# Raptor.net
KiCad netlist of a schematic drawn in Altium Designer
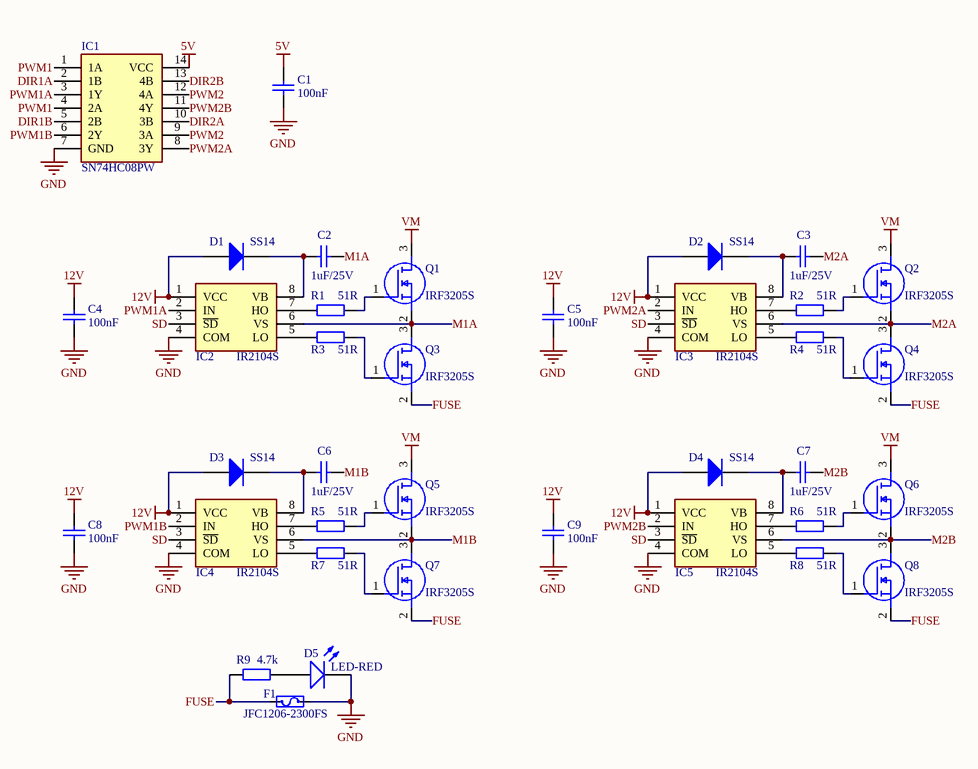
[diagram p0: Raptor.SchDoc]

(export (version "E")
  (design (tool "Eeschema 10.0.6"))
  (components
    (comp (ref "C1")
      (value "100nF")
      (footprint "CAP-0603")
      (description "贴片电容")
      (libsource (lib "Power_Lib_Altium") (part "CAP"))
    )
    (comp (ref "C2")
      (value "1uF/25V")
      (footprint "CAP-0603")
      (description "贴片电容")
      (libsource (lib "Power_Lib_Altium") (part "CAP"))
    )
    (comp (ref "C3")
      (value "1uF/25V")
      (footprint "CAP-0603")
      (description "贴片电容")
      (libsource (lib "Power_Lib_Altium") (part "CAP"))
    )
    (comp (ref "C4")
      (value "100nF")
      (footprint "CAP-0603")
      (description "贴片电容")
      (libsource (lib "Power_Lib_Altium") (part "CAP"))
    )
    (comp (ref "C5")
      (value "100nF")
      (footprint "CAP-0603")
      (description "贴片电容")
      (libsource (lib "Power_Lib_Altium") (part "CAP"))
    )
    (comp (ref "C6")
      (value "1uF/25V")
      (footprint "CAP-0603")
      (description "贴片电容")
      (libsource (lib "Power_Lib_Altium") (part "CAP"))
    )
    (comp (ref "C7")
      (value "1uF/25V")
      (footprint "CAP-0603")
      (description "贴片电容")
      (libsource (lib "Power_Lib_Altium") (part "CAP"))
    )
    (comp (ref "C8")
      (value "100nF")
      (footprint "CAP-0603")
      (description "贴片电容")
      (libsource (lib "Power_Lib_Altium") (part "CAP"))
    )
    (comp (ref "C9")
      (value "100nF")
      (footprint "CAP-0603")
      (description "贴片电容")
      (libsource (lib "Power_Lib_Altium") (part "CAP"))
    )
    (comp (ref "D1")
      (value "SS14")
      (footprint "DO-214AC_SMA")
      (description "二极管")
      (libsource (lib "Power_Lib_Altium") (part "DIODE"))
    )
    (comp (ref "D2")
      (value "SS14")
      (footprint "DO-214AC_SMA")
      (description "二极管")
      (libsource (lib "Power_Lib_Altium") (part "DIODE"))
    )
    (comp (ref "D3")
      (value "SS14")
      (footprint "DO-214AC_SMA")
      (description "二极管")
      (libsource (lib "Power_Lib_Altium") (part "DIODE"))
    )
    (comp (ref "D4")
      (value "SS14")
      (footprint "DO-214AC_SMA")
      (description "二极管")
      (libsource (lib "Power_Lib_Altium") (part "DIODE"))
    )
    (comp (ref "D5")
      (value "LED-RED")
      (footprint "LED-0603")
      (description "发光二极管")
      (libsource (lib "Power_Lib_Altium") (part "LED"))
    )
    (comp (ref "F1")
      (value "JFC1206-2300FS")
      (footprint "FUSE_1206")
      (description "一次性贴片保险丝")
      (libsource (lib "Power_Lib_Altium") (part "Fuse"))
    )
    (comp (ref "IC1")
      (value "SN74HC08PW")
      (footprint "TSSOP14")
      (description "Texas Instruments SN74HCT08PW")
      (fields (field (name "MANUFACTURER_PART_NUMBER") "SN74HCT08PW"))
      (libsource (lib "Power_Lib_Altium") (part "SN74HC08PW"))
    )
    (comp (ref "IC2")
      (value "IR2104S")
      (footprint "SOIC_8")
      (description "IC GATE DRVR HALF-BRIDGE 8SOIC")
      (libsource (lib "Power_Lib_Altium") (part "IR2104S"))
    )
    (comp (ref "IC3")
      (value "IR2104S")
      (footprint "SOIC_8")
      (description "IC GATE DRVR HALF-BRIDGE 8SOIC")
      (libsource (lib "Power_Lib_Altium") (part "IR2104S"))
    )
    (comp (ref "IC4")
      (value "IR2104S")
      (footprint "SOIC_8")
      (description "IC GATE DRVR HALF-BRIDGE 8SOIC")
      (libsource (lib "Power_Lib_Altium") (part "IR2104S"))
    )
    (comp (ref "IC5")
      (value "IR2104S")
      (footprint "SOIC_8")
      (description "IC GATE DRVR HALF-BRIDGE 8SOIC")
      (libsource (lib "Power_Lib_Altium") (part "IR2104S"))
    )
    (comp (ref "Q1")
      (value "IRF3205S")
      (footprint "D2PAK-3")
      (description "N 沟道 MOS")
      (fields (field (name "MANUFACTURER_PART_NUMBER") "SI2302DS") (field (name "RS PART NUMBER") "7983053P"))
      (libsource (lib "Power_Lib_Altium") (part "N-MOS"))
    )
    (comp (ref "Q2")
      (value "IRF3205S")
      (footprint "D2PAK-3")
      (description "N 沟道 MOS")
      (fields (field (name "MANUFACTURER_PART_NUMBER") "SI2302DS") (field (name "RS PART NUMBER") "7983053P"))
      (libsource (lib "Power_Lib_Altium") (part "N-MOS"))
    )
    (comp (ref "Q3")
      (value "IRF3205S")
      (footprint "D2PAK-3")
      (description "N 沟道 MOS")
      (fields (field (name "MANUFACTURER_PART_NUMBER") "SI2302DS") (field (name "RS PART NUMBER") "7983053P"))
      (libsource (lib "Power_Lib_Altium") (part "N-MOS"))
    )
    (comp (ref "Q4")
      (value "IRF3205S")
      (footprint "D2PAK-3")
      (description "N 沟道 MOS")
      (fields (field (name "MANUFACTURER_PART_NUMBER") "SI2302DS") (field (name "RS PART NUMBER") "7983053P"))
      (libsource (lib "Power_Lib_Altium") (part "N-MOS"))
    )
    (comp (ref "Q5")
      (value "IRF3205S")
      (footprint "D2PAK-3")
      (description "N 沟道 MOS")
      (fields (field (name "MANUFACTURER_PART_NUMBER") "SI2302DS") (field (name "RS PART NUMBER") "7983053P"))
      (libsource (lib "Power_Lib_Altium") (part "N-MOS"))
    )
    (comp (ref "Q6")
      (value "IRF3205S")
      (footprint "D2PAK-3")
      (description "N 沟道 MOS")
      (fields (field (name "MANUFACTURER_PART_NUMBER") "SI2302DS") (field (name "RS PART NUMBER") "7983053P"))
      (libsource (lib "Power_Lib_Altium") (part "N-MOS"))
    )
    (comp (ref "Q7")
      (value "IRF3205S")
      (footprint "D2PAK-3")
      (description "N 沟道 MOS")
      (fields (field (name "MANUFACTURER_PART_NUMBER") "SI2302DS") (field (name "RS PART NUMBER") "7983053P"))
      (libsource (lib "Power_Lib_Altium") (part "N-MOS"))
    )
    (comp (ref "Q8")
      (value "IRF3205S")
      (footprint "D2PAK-3")
      (description "N 沟道 MOS")
      (fields (field (name "MANUFACTURER_PART_NUMBER") "SI2302DS") (field (name "RS PART NUMBER") "7983053P"))
      (libsource (lib "Power_Lib_Altium") (part "N-MOS"))
    )
    (comp (ref "R1")
      (value "51R")
      (footprint "R-0603")
      (description "贴片电阻")
      (libsource (lib "Power_Lib_Altium") (part "RES"))
    )
    (comp (ref "R2")
      (value "51R")
      (footprint "R-0603")
      (description "贴片电阻")
      (libsource (lib "Power_Lib_Altium") (part "RES"))
    )
    (comp (ref "R3")
      (value "51R")
      (footprint "R-0603")
      (description "贴片电阻")
      (libsource (lib "Power_Lib_Altium") (part "RES"))
    )
    (comp (ref "R4")
      (value "51R")
      (footprint "R-0603")
      (description "贴片电阻")
      (libsource (lib "Power_Lib_Altium") (part "RES"))
    )
    (comp (ref "R5")
      (value "51R")
      (footprint "R-0603")
      (description "贴片电阻")
      (libsource (lib "Power_Lib_Altium") (part "RES"))
    )
    (comp (ref "R6")
      (value "51R")
      (footprint "R-0603")
      (description "贴片电阻")
      (libsource (lib "Power_Lib_Altium") (part "RES"))
    )
    (comp (ref "R7")
      (value "51R")
      (footprint "R-0603")
      (description "贴片电阻")
      (libsource (lib "Power_Lib_Altium") (part "RES"))
    )
    (comp (ref "R8")
      (value "51R")
      (footprint "R-0603")
      (description "贴片电阻")
      (libsource (lib "Power_Lib_Altium") (part "RES"))
    )
    (comp (ref "R9")
      (value "4.7k")
      (footprint "R-0603")
      (description "贴片电阻")
      (libsource (lib "Power_Lib_Altium") (part "RES"))
    )
  )
  (nets
    (net (code "1") (name "/DIR1A") (class "Default")
      (node (ref "IC1") (pin "2") (pinfunction "1B_2") (pintype "passive"))
    )
    (net (code "2") (name "/DIR1B") (class "Default")
      (node (ref "IC1") (pin "5") (pinfunction "2B_5") (pintype "passive"))
    )
    (net (code "3") (name "/DIR2A") (class "Default")
      (node (ref "IC1") (pin "10") (pinfunction "3B_10") (pintype "passive"))
    )
    (net (code "4") (name "/DIR2B") (class "Default")
      (node (ref "IC1") (pin "13") (pinfunction "4B_13") (pintype "passive"))
    )
    (net (code "5") (name "/FUSE") (class "Default")
      (node (ref "F1") (pin "1") (pinfunction "1_1") (pintype "passive"))
      (node (ref "Q3") (pin "2") (pinfunction "S_2") (pintype "passive"))
      (node (ref "Q4") (pin "2") (pinfunction "S_2") (pintype "passive"))
      (node (ref "Q7") (pin "2") (pinfunction "S_2") (pintype "passive"))
      (node (ref "Q8") (pin "2") (pinfunction "S_2") (pintype "passive"))
      (node (ref "R9") (pin "1") (pinfunction "1_1") (pintype "passive"))
    )
    (net (code "6") (name "/M1A") (class "Default")
      (node (ref "C2") (pin "2") (pinfunction "2_2") (pintype "passive"))
      (node (ref "IC2") (pin "6") (pinfunction "VS_6") (pintype "passive"))
      (node (ref "Q1") (pin "2") (pinfunction "S_2") (pintype "passive"))
      (node (ref "Q3") (pin "3") (pinfunction "D_3") (pintype "passive"))
    )
    (net (code "7") (name "/M1B") (class "Default")
      (node (ref "C6") (pin "2") (pinfunction "2_2") (pintype "passive"))
      (node (ref "IC4") (pin "6") (pinfunction "VS_6") (pintype "passive"))
      (node (ref "Q5") (pin "2") (pinfunction "S_2") (pintype "passive"))
      (node (ref "Q7") (pin "3") (pinfunction "D_3") (pintype "passive"))
    )
    (net (code "8") (name "/M2A") (class "Default")
      (node (ref "C3") (pin "2") (pinfunction "2_2") (pintype "passive"))
      (node (ref "IC3") (pin "6") (pinfunction "VS_6") (pintype "passive"))
      (node (ref "Q2") (pin "2") (pinfunction "S_2") (pintype "passive"))
      (node (ref "Q4") (pin "3") (pinfunction "D_3") (pintype "passive"))
    )
    (net (code "9") (name "/M2B") (class "Default")
      (node (ref "C7") (pin "2") (pinfunction "2_2") (pintype "passive"))
      (node (ref "IC5") (pin "6") (pinfunction "VS_6") (pintype "passive"))
      (node (ref "Q6") (pin "2") (pinfunction "S_2") (pintype "passive"))
      (node (ref "Q8") (pin "3") (pinfunction "D_3") (pintype "passive"))
    )
    (net (code "10") (name "/PWM1") (class "Default")
      (node (ref "IC1") (pin "1") (pinfunction "1A_1") (pintype "passive"))
      (node (ref "IC1") (pin "4") (pinfunction "2A_4") (pintype "passive"))
    )
    (net (code "11") (name "/PWM1A") (class "Default")
      (node (ref "IC1") (pin "3") (pinfunction "1Y_3") (pintype "passive"))
      (node (ref "IC2") (pin "2") (pinfunction "IN_2") (pintype "passive"))
    )
    (net (code "12") (name "/PWM1B") (class "Default")
      (node (ref "IC1") (pin "6") (pinfunction "2Y_6") (pintype "passive"))
      (node (ref "IC4") (pin "2") (pinfunction "IN_2") (pintype "passive"))
    )
    (net (code "13") (name "/PWM2") (class "Default")
      (node (ref "IC1") (pin "12") (pinfunction "4A_12") (pintype "passive"))
      (node (ref "IC1") (pin "9") (pinfunction "3A_9") (pintype "passive"))
    )
    (net (code "14") (name "/PWM2A") (class "Default")
      (node (ref "IC1") (pin "8") (pinfunction "3Y_8") (pintype "passive"))
      (node (ref "IC3") (pin "2") (pinfunction "IN_2") (pintype "passive"))
    )
    (net (code "15") (name "/PWM2B") (class "Default")
      (node (ref "IC1") (pin "11") (pinfunction "4Y_11") (pintype "passive"))
      (node (ref "IC5") (pin "2") (pinfunction "IN_2") (pintype "passive"))
    )
    (net (code "16") (name "/SD") (class "Default")
      (node (ref "IC2") (pin "3") (pinfunction "~{SD}_3") (pintype "passive"))
      (node (ref "IC3") (pin "3") (pinfunction "~{SD}_3") (pintype "passive"))
      (node (ref "IC4") (pin "3") (pinfunction "~{SD}_3") (pintype "passive"))
      (node (ref "IC5") (pin "3") (pinfunction "~{SD}_3") (pintype "passive"))
    )
    (net (code "17") (name "5V") (class "Default")
      (node (ref "C1") (pin "2") (pinfunction "2_2") (pintype "passive"))
      (node (ref "IC1") (pin "14") (pinfunction "VCC_14") (pintype "passive"))
    )
    (net (code "18") (name "12V") (class "Default")
      (node (ref "C4") (pin "2") (pinfunction "2_2") (pintype "passive"))
      (node (ref "C5") (pin "2") (pinfunction "2_2") (pintype "passive"))
      (node (ref "C8") (pin "2") (pinfunction "2_2") (pintype "passive"))
      (node (ref "C9") (pin "2") (pinfunction "2_2") (pintype "passive"))
      (node (ref "D1") (pin "1") (pinfunction "A_1") (pintype "passive"))
      (node (ref "D2") (pin "1") (pinfunction "A_1") (pintype "passive"))
      (node (ref "D3") (pin "1") (pinfunction "A_1") (pintype "passive"))
      (node (ref "D4") (pin "1") (pinfunction "A_1") (pintype "passive"))
      (node (ref "IC2") (pin "1") (pinfunction "VCC_1") (pintype "passive"))
      (node (ref "IC3") (pin "1") (pinfunction "VCC_1") (pintype "passive"))
      (node (ref "IC4") (pin "1") (pinfunction "VCC_1") (pintype "passive"))
      (node (ref "IC5") (pin "1") (pinfunction "VCC_1") (pintype "passive"))
    )
    (net (code "19") (name "GND") (class "Default")
      (node (ref "C1") (pin "1") (pinfunction "1_1") (pintype "passive"))
      (node (ref "C4") (pin "1") (pinfunction "1_1") (pintype "passive"))
      (node (ref "C5") (pin "1") (pinfunction "1_1") (pintype "passive"))
      (node (ref "C8") (pin "1") (pinfunction "1_1") (pintype "passive"))
      (node (ref "C9") (pin "1") (pinfunction "1_1") (pintype "passive"))
      (node (ref "D5") (pin "K") (pinfunction "K_K") (pintype "passive"))
      (node (ref "F1") (pin "2") (pinfunction "2_2") (pintype "passive"))
      (node (ref "IC1") (pin "7") (pinfunction "GND_7") (pintype "passive"))
      (node (ref "IC2") (pin "4") (pinfunction "COM_4") (pintype "passive"))
      (node (ref "IC3") (pin "4") (pinfunction "COM_4") (pintype "passive"))
      (node (ref "IC4") (pin "4") (pinfunction "COM_4") (pintype "passive"))
      (node (ref "IC5") (pin "4") (pinfunction "COM_4") (pintype "passive"))
    )
    (net (code "20") (name "Net-(D1-K)") (class "Default")
      (node (ref "C2") (pin "1") (pinfunction "1_1") (pintype "passive"))
      (node (ref "D1") (pin "2") (pinfunction "K_2") (pintype "passive"))
      (node (ref "IC2") (pin "8") (pinfunction "VB_8") (pintype "passive"))
    )
    (net (code "21") (name "Net-(D2-K)") (class "Default")
      (node (ref "C3") (pin "1") (pinfunction "1_1") (pintype "passive"))
      (node (ref "D2") (pin "2") (pinfunction "K_2") (pintype "passive"))
      (node (ref "IC3") (pin "8") (pinfunction "VB_8") (pintype "passive"))
    )
    (net (code "22") (name "Net-(D3-K)") (class "Default")
      (node (ref "C6") (pin "1") (pinfunction "1_1") (pintype "passive"))
      (node (ref "D3") (pin "2") (pinfunction "K_2") (pintype "passive"))
      (node (ref "IC4") (pin "8") (pinfunction "VB_8") (pintype "passive"))
    )
    (net (code "23") (name "Net-(D4-K)") (class "Default")
      (node (ref "C7") (pin "1") (pinfunction "1_1") (pintype "passive"))
      (node (ref "D4") (pin "2") (pinfunction "K_2") (pintype "passive"))
      (node (ref "IC5") (pin "8") (pinfunction "VB_8") (pintype "passive"))
    )
    (net (code "24") (name "Net-(D5-PadA)") (class "Default")
      (node (ref "D5") (pin "A") (pinfunction "A_A") (pintype "passive"))
      (node (ref "R9") (pin "2") (pinfunction "2_2") (pintype "passive"))
    )
    (net (code "25") (name "Net-(IC2-HO)") (class "Default")
      (node (ref "IC2") (pin "7") (pinfunction "HO_7") (pintype "passive"))
      (node (ref "R1") (pin "1") (pinfunction "1_1") (pintype "passive"))
    )
    (net (code "26") (name "Net-(IC2-LO)") (class "Default")
      (node (ref "IC2") (pin "5") (pinfunction "LO_5") (pintype "passive"))
      (node (ref "R3") (pin "1") (pinfunction "1_1") (pintype "passive"))
    )
    (net (code "27") (name "Net-(IC3-HO)") (class "Default")
      (node (ref "IC3") (pin "7") (pinfunction "HO_7") (pintype "passive"))
      (node (ref "R2") (pin "1") (pinfunction "1_1") (pintype "passive"))
    )
    (net (code "28") (name "Net-(IC3-LO)") (class "Default")
      (node (ref "IC3") (pin "5") (pinfunction "LO_5") (pintype "passive"))
      (node (ref "R4") (pin "1") (pinfunction "1_1") (pintype "passive"))
    )
    (net (code "29") (name "Net-(IC4-HO)") (class "Default")
      (node (ref "IC4") (pin "7") (pinfunction "HO_7") (pintype "passive"))
      (node (ref "R5") (pin "1") (pinfunction "1_1") (pintype "passive"))
    )
    (net (code "30") (name "Net-(IC4-LO)") (class "Default")
      (node (ref "IC4") (pin "5") (pinfunction "LO_5") (pintype "passive"))
      (node (ref "R7") (pin "1") (pinfunction "1_1") (pintype "passive"))
    )
    (net (code "31") (name "Net-(IC5-HO)") (class "Default")
      (node (ref "IC5") (pin "7") (pinfunction "HO_7") (pintype "passive"))
      (node (ref "R6") (pin "1") (pinfunction "1_1") (pintype "passive"))
    )
    (net (code "32") (name "Net-(IC5-LO)") (class "Default")
      (node (ref "IC5") (pin "5") (pinfunction "LO_5") (pintype "passive"))
      (node (ref "R8") (pin "1") (pinfunction "1_1") (pintype "passive"))
    )
    (net (code "33") (name "Net-(Q1-G)") (class "Default")
      (node (ref "Q1") (pin "1") (pinfunction "G_1") (pintype "passive"))
      (node (ref "R1") (pin "2") (pinfunction "2_2") (pintype "passive"))
    )
    (net (code "34") (name "Net-(Q2-G)") (class "Default")
      (node (ref "Q2") (pin "1") (pinfunction "G_1") (pintype "passive"))
      (node (ref "R2") (pin "2") (pinfunction "2_2") (pintype "passive"))
    )
    (net (code "35") (name "Net-(Q3-G)") (class "Default")
      (node (ref "Q3") (pin "1") (pinfunction "G_1") (pintype "passive"))
      (node (ref "R3") (pin "2") (pinfunction "2_2") (pintype "passive"))
    )
    (net (code "36") (name "Net-(Q4-G)") (class "Default")
      (node (ref "Q4") (pin "1") (pinfunction "G_1") (pintype "passive"))
      (node (ref "R4") (pin "2") (pinfunction "2_2") (pintype "passive"))
    )
    (net (code "37") (name "Net-(Q5-G)") (class "Default")
      (node (ref "Q5") (pin "1") (pinfunction "G_1") (pintype "passive"))
      (node (ref "R5") (pin "2") (pinfunction "2_2") (pintype "passive"))
    )
    (net (code "38") (name "Net-(Q6-G)") (class "Default")
      (node (ref "Q6") (pin "1") (pinfunction "G_1") (pintype "passive"))
      (node (ref "R6") (pin "2") (pinfunction "2_2") (pintype "passive"))
    )
    (net (code "39") (name "Net-(Q7-G)") (class "Default")
      (node (ref "Q7") (pin "1") (pinfunction "G_1") (pintype "passive"))
      (node (ref "R7") (pin "2") (pinfunction "2_2") (pintype "passive"))
    )
    (net (code "40") (name "Net-(Q8-G)") (class "Default")
      (node (ref "Q8") (pin "1") (pinfunction "G_1") (pintype "passive"))
      (node (ref "R8") (pin "2") (pinfunction "2_2") (pintype "passive"))
    )
    (net (code "41") (name "VM") (class "Default")
      (node (ref "Q1") (pin "3") (pinfunction "D_3") (pintype "passive"))
      (node (ref "Q2") (pin "3") (pinfunction "D_3") (pintype "passive"))
      (node (ref "Q5") (pin "3") (pinfunction "D_3") (pintype "passive"))
      (node (ref "Q6") (pin "3") (pinfunction "D_3") (pintype "passive"))
    )
  )
)
